# POW_MCU.net
KiCad netlist of a schematic drawn in Altium Designer
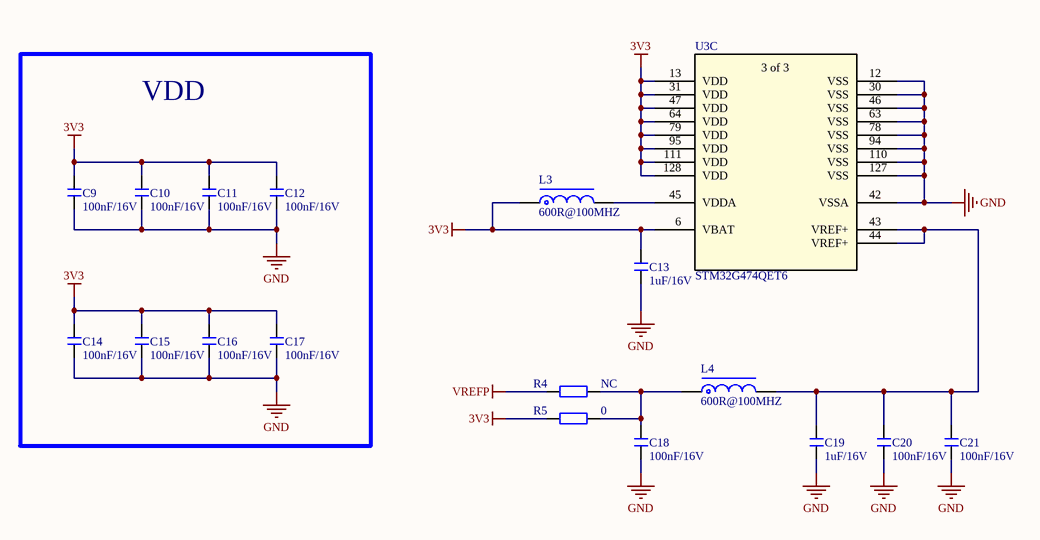
[diagram p0: POW_MCU.SchDoc]

(export (version "E")
  (design (tool "Eeschema 10.0.6"))
  (components
    (comp (ref "C9")
      (value "100nF/16V")
      (footprint "C 0402_L")
      (description "贴片电容")
      (libsource (lib "3.1   - 电阻-电容-电感") (part "C"))
    )
    (comp (ref "C10")
      (value "100nF/16V")
      (footprint "C 0402_L")
      (description "贴片电容")
      (libsource (lib "3.1   - 电阻-电容-电感") (part "C"))
    )
    (comp (ref "C11")
      (value "100nF/16V")
      (footprint "C 0402_L")
      (description "贴片电容")
      (libsource (lib "3.1   - 电阻-电容-电感") (part "C"))
    )
    (comp (ref "C12")
      (value "100nF/16V")
      (footprint "C 0402_L")
      (description "贴片电容")
      (libsource (lib "3.1   - 电阻-电容-电感") (part "C"))
    )
    (comp (ref "C13")
      (value "1uF/16V")
      (footprint "C 0402_L")
      (description "贴片电容")
      (libsource (lib "3.1   - 电阻-电容-电感") (part "C"))
    )
    (comp (ref "C14")
      (value "100nF/16V")
      (footprint "C 0402_L")
      (description "贴片电容")
      (libsource (lib "3.1   - 电阻-电容-电感") (part "C"))
    )
    (comp (ref "C15")
      (value "100nF/16V")
      (footprint "C 0402_L")
      (description "贴片电容")
      (libsource (lib "3.1   - 电阻-电容-电感") (part "C"))
    )
    (comp (ref "C16")
      (value "100nF/16V")
      (footprint "C 0402_L")
      (description "贴片电容")
      (libsource (lib "3.1   - 电阻-电容-电感") (part "C"))
    )
    (comp (ref "C17")
      (value "100nF/16V")
      (footprint "C 0402_L")
      (description "贴片电容")
      (libsource (lib "3.1   - 电阻-电容-电感") (part "C"))
    )
    (comp (ref "C18")
      (value "100nF/16V")
      (footprint "C 0402_L")
      (description "贴片电容")
      (libsource (lib "3.1   - 电阻-电容-电感") (part "C"))
    )
    (comp (ref "C19")
      (value "1uF/16V")
      (footprint "C 0402_L")
      (description "贴片电容")
      (libsource (lib "3.1   - 电阻-电容-电感") (part "C"))
    )
    (comp (ref "C20")
      (value "100nF/16V")
      (footprint "C 0402_L")
      (description "贴片电容")
      (libsource (lib "3.1   - 电阻-电容-电感") (part "C"))
    )
    (comp (ref "C21")
      (value "100nF/16V")
      (footprint "C 0402_L")
      (description "贴片电容")
      (libsource (lib "3.1   - 电阻-电容-电感") (part "C"))
    )
    (comp (ref "L3")
      (value "600R@100MHZ")
      (footprint "L 0603")
      (description "XFL4020-222MEB")
      (libsource (lib "3.1   - 电阻-电容-电感") (part "L-CD"))
    )
    (comp (ref "L4")
      (value "600R@100MHZ")
      (footprint "L 0603")
      (description "XFL4020-222MEB")
      (libsource (lib "3.1   - 电阻-电容-电感") (part "L-CD"))
    )
    (comp (ref "R4")
      (value "NC")
      (footprint "R 0402_L")
      (description "贴片电阻")
      (libsource (lib "3.1   - 电阻-电容-电感") (part "R"))
    )
    (comp (ref "R5")
      (value "0")
      (footprint "R 0402_L")
      (description "贴片电阻")
      (libsource (lib "3.1   - 电阻-电容-电感") (part "R"))
    )
    (comp (ref "U3")
      (value "STM32G474QET6")
      (footprint "LQFP128-14*14")
      (description "No Description Available")
      (libsource (lib "2021-04-22_13-53-57") (part "STM32G474QET6"))
    )
  )
  (nets
    (net (code "1") (name "3V3") (class "Default")
      (node (ref "C10") (pin "2") (pinfunction "2_2") (pintype "passive"))
      (node (ref "C11") (pin "2") (pinfunction "2_2") (pintype "passive"))
      (node (ref "C12") (pin "2") (pinfunction "2_2") (pintype "passive"))
      (node (ref "C13") (pin "1") (pinfunction "1_1") (pintype "passive"))
      (node (ref "C14") (pin "2") (pinfunction "2_2") (pintype "passive"))
      (node (ref "C15") (pin "2") (pinfunction "2_2") (pintype "passive"))
      (node (ref "C16") (pin "2") (pinfunction "2_2") (pintype "passive"))
      (node (ref "C17") (pin "2") (pinfunction "2_2") (pintype "passive"))
      (node (ref "C9") (pin "2") (pinfunction "2_2") (pintype "passive"))
      (node (ref "L3") (pin "1") (pinfunction "1_1") (pintype "passive"))
      (node (ref "R5") (pin "1") (pinfunction "1_1") (pintype "passive"))
      (node (ref "U3") (pin "111") (pinfunction "VDD_111") (pintype "power_in"))
      (node (ref "U3") (pin "128") (pinfunction "VDD_128") (pintype "power_in"))
      (node (ref "U3") (pin "13") (pinfunction "VDD_13") (pintype "power_in"))
      (node (ref "U3") (pin "31") (pinfunction "VDD_31") (pintype "power_in"))
      (node (ref "U3") (pin "47") (pinfunction "VDD_47") (pintype "power_in"))
      (node (ref "U3") (pin "6") (pinfunction "VBAT_6") (pintype "power_in"))
      (node (ref "U3") (pin "64") (pinfunction "VDD_64") (pintype "power_in"))
      (node (ref "U3") (pin "79") (pinfunction "VDD_79") (pintype "power_in"))
      (node (ref "U3") (pin "95") (pinfunction "VDD_95") (pintype "power_in"))
    )
    (net (code "2") (name "GND") (class "Default")
      (node (ref "C10") (pin "1") (pinfunction "1_1") (pintype "passive"))
      (node (ref "C11") (pin "1") (pinfunction "1_1") (pintype "passive"))
      (node (ref "C12") (pin "1") (pinfunction "1_1") (pintype "passive"))
      (node (ref "C13") (pin "2") (pinfunction "2_2") (pintype "passive"))
      (node (ref "C14") (pin "1") (pinfunction "1_1") (pintype "passive"))
      (node (ref "C15") (pin "1") (pinfunction "1_1") (pintype "passive"))
      (node (ref "C16") (pin "1") (pinfunction "1_1") (pintype "passive"))
      (node (ref "C17") (pin "1") (pinfunction "1_1") (pintype "passive"))
      (node (ref "C18") (pin "1") (pinfunction "1_1") (pintype "passive"))
      (node (ref "C19") (pin "2") (pinfunction "2_2") (pintype "passive"))
      (node (ref "C20") (pin "1") (pinfunction "1_1") (pintype "passive"))
      (node (ref "C21") (pin "1") (pinfunction "1_1") (pintype "passive"))
      (node (ref "C9") (pin "1") (pinfunction "1_1") (pintype "passive"))
      (node (ref "U3") (pin "110") (pinfunction "VSS_110") (pintype "power_in"))
      (node (ref "U3") (pin "12") (pinfunction "VSS_12") (pintype "power_in"))
      (node (ref "U3") (pin "127") (pinfunction "VSS_127") (pintype "power_in"))
      (node (ref "U3") (pin "30") (pinfunction "VSS_30") (pintype "power_in"))
      (node (ref "U3") (pin "42") (pinfunction "VSSA_42") (pintype "power_in"))
      (node (ref "U3") (pin "46") (pinfunction "VSS_46") (pintype "power_in"))
      (node (ref "U3") (pin "63") (pinfunction "VSS_63") (pintype "power_in"))
      (node (ref "U3") (pin "78") (pinfunction "VSS_78") (pintype "power_in"))
      (node (ref "U3") (pin "94") (pinfunction "VSS_94") (pintype "power_in"))
    )
    (net (code "3") (name "Net-(C18-Pad2)") (class "Default")
      (node (ref "C18") (pin "2") (pinfunction "2_2") (pintype "passive"))
      (node (ref "L4") (pin "1") (pinfunction "1_1") (pintype "passive"))
      (node (ref "R4") (pin "2") (pinfunction "2_2") (pintype "passive"))
      (node (ref "R5") (pin "2") (pinfunction "2_2") (pintype "passive"))
    )
    (net (code "4") (name "Net-(C19-Pad1)") (class "Default")
      (node (ref "C19") (pin "1") (pinfunction "1_1") (pintype "passive"))
      (node (ref "C20") (pin "2") (pinfunction "2_2") (pintype "passive"))
      (node (ref "C21") (pin "2") (pinfunction "2_2") (pintype "passive"))
      (node (ref "L4") (pin "2") (pinfunction "2_2") (pintype "passive"))
      (node (ref "U3") (pin "43") (pinfunction "VREF+_43") (pintype "power_in"))
      (node (ref "U3") (pin "44") (pinfunction "VREF+_44") (pintype "power_in"))
    )
    (net (code "5") (name "Net-(U3C-VDDA)") (class "Default")
      (node (ref "L3") (pin "2") (pinfunction "2_2") (pintype "passive"))
      (node (ref "U3") (pin "45") (pinfunction "VDDA_45") (pintype "power_in"))
    )
    (net (code "6") (name "VREFP") (class "Default")
      (node (ref "R4") (pin "1") (pinfunction "1_1") (pintype "passive"))
    )
  )
)
